# design.net
KiCad netlist of a schematic drawn in Altium Designer
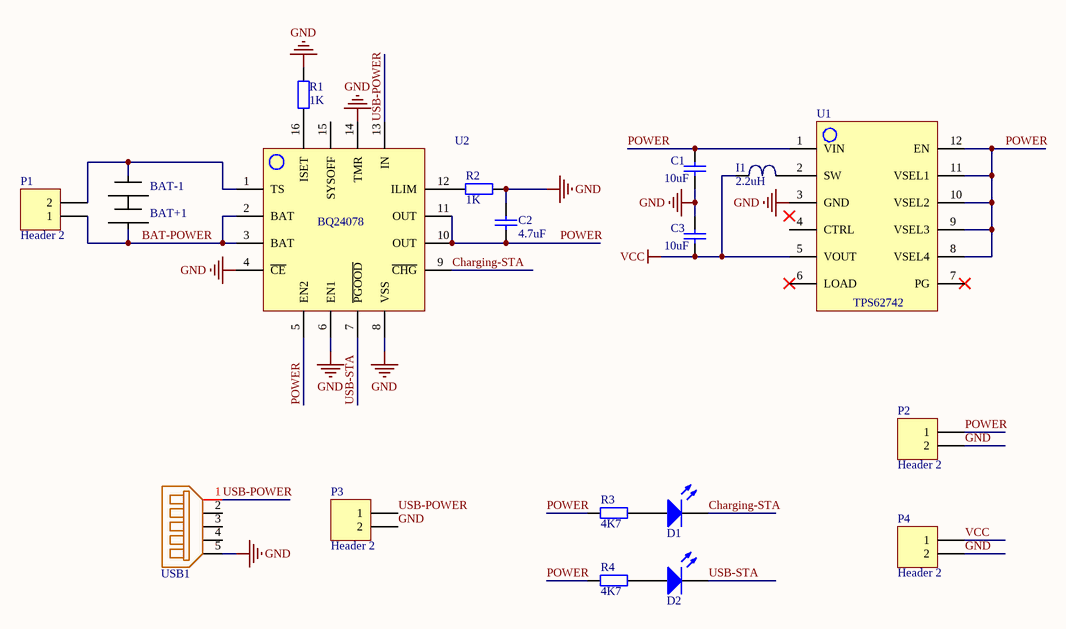
[diagram p0: 电池模块_原理图.SchDoc]

(export (version "E")
  (design (tool "Eeschema 10.0.6"))
  (components
    (comp (ref "BAT+1") (value "BAT") (footprint "BAT+") (libsource (lib "原理图库") (part "BAT")))
    (comp (ref "BAT-1") (value "BAT") (footprint "BTA-") (libsource (lib "原理图库") (part "BAT")))
    (comp (ref "C1")
      (value "10uF")
      (footprint "1__0603-CAP_")
      (description "Capacitor")
      (libsource (lib "Miscellaneous Devices") (part "Cap"))
    )
    (comp (ref "C2")
      (value "4.7uF")
      (footprint "1__0603-CAP_")
      (description "Capacitor")
      (libsource (lib "Miscellaneous Devices") (part "Cap"))
    )
    (comp (ref "C3")
      (value "10uF")
      (footprint "1__0603-CAP_")
      (description "Capacitor")
      (libsource (lib "Miscellaneous Devices") (part "Cap"))
    )
    (comp (ref "D1")
      (value "LED")
      (footprint "1__0603-LED_")
      (description "Typical INFRARED GaAs LED")
      (libsource (lib "Miscellaneous Devices") (part "LED0"))
    )
    (comp (ref "D2")
      (value "LED")
      (footprint "1__0603-LED_")
      (description "Typical INFRARED GaAs LED")
      (libsource (lib "Miscellaneous Devices") (part "LED0"))
    )
    (comp (ref "I1") (value "2.2uH") (footprint "1__0805_IND") (libsource (lib "常用原理图_by_K") (part "电感")))
    (comp (ref "P1")
      (value "Header 2")
      (footprint "HDR1X2")
      (description "Header, 2-Pin")
      (fields (field (name "PUBLISHER") "Altium Limited"))
      (libsource (lib "") (part "Header 2_1"))
    )
    (comp (ref "P2")
      (value "Header 2")
      (footprint "HDR1X2")
      (description "Header, 2-Pin")
      (fields (field (name "PUBLISHER") "Altium Limited"))
      (libsource (lib "!)Miscellaneous Integrated Library") (part "Header 2"))
    )
    (comp (ref "P3")
      (value "Header 2")
      (footprint "HDR1X2")
      (description "Header, 2-Pin")
      (fields (field (name "PUBLISHER") "Altium Limited"))
      (libsource (lib "!)Miscellaneous Integrated Library") (part "Header 2"))
    )
    (comp (ref "P4")
      (value "Header 2")
      (footprint "HDR1X2")
      (description "Header, 2-Pin")
      (fields (field (name "PUBLISHER") "Altium Limited"))
      (libsource (lib "!)Miscellaneous Integrated Library") (part "Header 2"))
    )
    (comp (ref "R1")
      (value "1K")
      (footprint "1__0603-RES_")
      (description "Resistor")
      (libsource (lib "") (part "Res2_2"))
    )
    (comp (ref "R2")
      (value "1K")
      (footprint "1__0603-RES_")
      (description "Resistor")
      (libsource (lib "") (part "Res2_1"))
    )
    (comp (ref "R3")
      (value "4K7")
      (footprint "1__0603-RES_")
      (description "Resistor")
      (libsource (lib "Miscellaneous Devices") (part "Res2"))
    )
    (comp (ref "R4")
      (value "4K7")
      (footprint "1__0603-RES_")
      (description "Resistor")
      (libsource (lib "Miscellaneous Devices") (part "Res2"))
    )
    (comp (ref "U1")
      (value "TPS62742")
      (footprint "TPS62742")
      (description "锂电池稳压")
      (libsource (lib "原理图库") (part "TPS62742"))
    )
    (comp (ref "U2")
      (value "BQ24078")
      (footprint "BQ24078")
      (description "充电芯片")
      (libsource (lib "原理图库") (part "BQ24078"))
    )
    (comp (ref "USB1")
      (value "USB-5P")
      (footprint "1__Micro USB 立贴_")
      (description "USB CONNECTOR")
      (libsource (lib "!)Miscellaneous Integrated Library") (part "USB-5P"))
    )
  )
  (nets
    (net (code "1") (name "/BAT-POWER") (class "Default")
      (node (ref "BAT+1") (pin "1") (pintype "passive"))
      (node (ref "P1") (pin "1") (pinfunction "1_1") (pintype "passive"))
      (node (ref "U2") (pin "2") (pinfunction "BAT_2") (pintype "passive"))
      (node (ref "U2") (pin "3") (pinfunction "BAT_3") (pintype "passive"))
    )
    (net (code "2") (name "/Charging-STA") (class "Default")
      (node (ref "D1") (pin "2") (pinfunction "2_2") (pintype "passive"))
      (node (ref "U2") (pin "9") (pinfunction "~{CHG}_9") (pintype "passive"))
    )
    (net (code "3") (name "/POWER") (class "Default")
      (node (ref "C1") (pin "2") (pinfunction "2_2") (pintype "passive"))
      (node (ref "C2") (pin "1") (pinfunction "1_1") (pintype "passive"))
      (node (ref "P2") (pin "1") (pinfunction "1_1") (pintype "passive"))
      (node (ref "R3") (pin "1") (pinfunction "1_1") (pintype "passive"))
      (node (ref "R4") (pin "1") (pinfunction "1_1") (pintype "passive"))
      (node (ref "U1") (pin "1") (pinfunction "VIN_1") (pintype "passive"))
      (node (ref "U1") (pin "10") (pinfunction "VSEL2_10") (pintype "passive"))
      (node (ref "U1") (pin "11") (pinfunction "VSEL1_11") (pintype "passive"))
      (node (ref "U1") (pin "12") (pinfunction "EN_12") (pintype "passive"))
      (node (ref "U1") (pin "8") (pinfunction "VSEL4_8") (pintype "passive"))
      (node (ref "U1") (pin "9") (pinfunction "VSEL3_9") (pintype "passive"))
      (node (ref "U2") (pin "10") (pinfunction "OUT_10") (pintype "passive"))
      (node (ref "U2") (pin "11") (pinfunction "OUT_11") (pintype "passive"))
      (node (ref "U2") (pin "5") (pinfunction "EN2_5") (pintype "passive"))
    )
    (net (code "4") (name "/USB-POWER") (class "Default")
      (node (ref "P3") (pin "1") (pinfunction "1_1") (pintype "passive"))
      (node (ref "U2") (pin "13") (pinfunction "IN_13") (pintype "passive"))
      (node (ref "USB1") (pin "1") (pinfunction "VBUS_1") (pintype "passive"))
    )
    (net (code "5") (name "/USB-STA") (class "Default")
      (node (ref "D2") (pin "2") (pinfunction "2_2") (pintype "passive"))
      (node (ref "U2") (pin "7") (pinfunction "~{PGOOD}_7") (pintype "passive"))
    )
    (net (code "6") (name "GND") (class "Default")
      (node (ref "C1") (pin "1") (pinfunction "1_1") (pintype "passive"))
      (node (ref "C2") (pin "2") (pinfunction "2_2") (pintype "passive"))
      (node (ref "C3") (pin "2") (pinfunction "2_2") (pintype "passive"))
      (node (ref "P2") (pin "2") (pinfunction "2_2") (pintype "passive"))
      (node (ref "P3") (pin "2") (pinfunction "2_2") (pintype "passive"))
      (node (ref "P4") (pin "2") (pinfunction "2_2") (pintype "passive"))
      (node (ref "R1") (pin "1") (pinfunction "1_1") (pintype "passive"))
      (node (ref "R2") (pin "1") (pinfunction "1_1") (pintype "passive"))
      (node (ref "U1") (pin "3") (pinfunction "GND_3") (pintype "passive"))
      (node (ref "U2") (pin "14") (pinfunction "TMR_14") (pintype "passive"))
      (node (ref "U2") (pin "4") (pinfunction "~{CE}_4") (pintype "passive"))
      (node (ref "U2") (pin "6") (pinfunction "EN1_6") (pintype "passive"))
      (node (ref "U2") (pin "8") (pinfunction "VSS_8") (pintype "passive"))
      (node (ref "USB1") (pin "5") (pinfunction "GND_5") (pintype "passive"))
    )
    (net (code "7") (name "Net-(BAT+1-Pad2)") (class "Default")
      (node (ref "BAT+1") (pin "2") (pintype "passive"))
      (node (ref "BAT-1") (pin "1") (pintype "passive"))
    )
    (net (code "8") (name "Net-(D1-Pad1)") (class "Default")
      (node (ref "D1") (pin "1") (pinfunction "1_1") (pintype "passive"))
      (node (ref "R3") (pin "2") (pinfunction "2_2") (pintype "passive"))
    )
    (net (code "9") (name "Net-(D2-Pad1)") (class "Default")
      (node (ref "D2") (pin "1") (pinfunction "1_1") (pintype "passive"))
      (node (ref "R4") (pin "2") (pinfunction "2_2") (pintype "passive"))
    )
    (net (code "10") (name "Net-(U1-SW)") (class "Default")
      (node (ref "I1") (pin "2") (pinfunction "2_2") (pintype "passive"))
      (node (ref "U1") (pin "2") (pinfunction "SW_2") (pintype "passive"))
    )
    (net (code "11") (name "Net-(U2-ILIM)") (class "Default")
      (node (ref "R2") (pin "2") (pinfunction "2_2") (pintype "passive"))
      (node (ref "U2") (pin "12") (pinfunction "ILIM_12") (pintype "passive"))
    )
    (net (code "12") (name "Net-(U2-ISET)") (class "Default")
      (node (ref "R1") (pin "2") (pinfunction "2_2") (pintype "passive"))
      (node (ref "U2") (pin "16") (pinfunction "ISET_16") (pintype "passive"))
    )
    (net (code "13") (name "Net-(U2-TS)") (class "Default")
      (node (ref "BAT-1") (pin "2") (pintype "passive"))
      (node (ref "P1") (pin "2") (pinfunction "2_2") (pintype "passive"))
      (node (ref "U2") (pin "1") (pinfunction "TS_1") (pintype "passive"))
    )
    (net (code "14") (name "VCC") (class "Default")
      (node (ref "C3") (pin "1") (pinfunction "1_1") (pintype "passive"))
      (node (ref "I1") (pin "1") (pinfunction "1_1") (pintype "passive"))
      (node (ref "P4") (pin "1") (pinfunction "1_1") (pintype "passive"))
      (node (ref "U1") (pin "5") (pinfunction "VOUT_5") (pintype "passive"))
    )
    (net (code "15") (name "unconnected-(U1-CTRL-Pad4)") (class "Default")
      (node (ref "U1") (pin "4") (pinfunction "CTRL_4") (pintype "passive"))
    )
    (net (code "16") (name "unconnected-(U1-LOAD-Pad6)") (class "Default")
      (node (ref "U1") (pin "6") (pinfunction "LOAD_6") (pintype "passive+no_connect"))
    )
    (net (code "17") (name "unconnected-(U1-PG-Pad7)") (class "Default")
      (node (ref "U1") (pin "7") (pinfunction "PG_7") (pintype "passive+no_connect"))
    )
    (net (code "18") (name "unconnected-(U2-SYSOFF-Pad15)") (class "Default")
      (node (ref "U2") (pin "15") (pinfunction "SYSOFF_15") (pintype "passive"))
    )
    (net (code "19") (name "unconnected-(USB1-D+-Pad3)") (class "Default")
      (node (ref "USB1") (pin "3") (pinfunction "D+_3") (pintype "passive"))
    )
    (net (code "20") (name "unconnected-(USB1-D--Pad2)") (class "Default")
      (node (ref "USB1") (pin "2") (pinfunction "D-_2") (pintype "passive"))
    )
    (net (code "21") (name "unconnected-(USB1-ID-Pad4)") (class "Default")
      (node (ref "USB1") (pin "4") (pinfunction "ID_4") (pintype "passive"))
    )
  )
)
